# Tablet_LPF.net
KiCad netlist of a schematic drawn in EAGLE
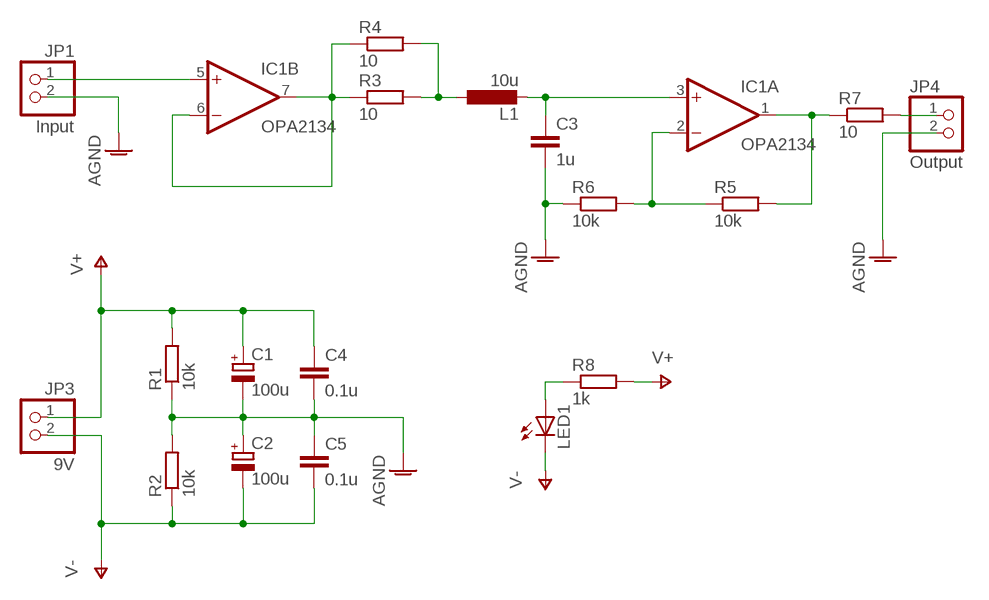
[diagram p0: schematic, sheet 1]

(export (version "E")
  (design (tool "Eeschema 10.0.6"))
  (components
    (comp (ref "C1")
      (value "100u")
      (footprint "eagle-import:E2,5-7")
      (libsource (lib "eagle-import") (part "CPOL-EUE2.5-7"))
    )
    (comp (ref "C2")
      (value "100u")
      (footprint "eagle-import:E2,5-7")
      (libsource (lib "eagle-import") (part "CPOL-EUE2.5-7"))
    )
    (comp (ref "C3")
      (value "1u")
      (footprint "eagle-import:C050-045X075")
      (libsource (lib "eagle-import") (part "C-EU050-045X075"))
    )
    (comp (ref "C4")
      (value "0.1u")
      (footprint "eagle-import:C025-024X044")
      (libsource (lib "eagle-import") (part "C-EU025-024X044"))
    )
    (comp (ref "C5")
      (value "0.1u")
      (footprint "eagle-import:C025-024X044")
      (libsource (lib "eagle-import") (part "C-EU025-024X044"))
    )
    (comp (ref "IC1")
      (value "OPA2134")
      (footprint "eagle-import:DIL08")
      (libsource (lib "eagle-import") (part "LM358N"))
    )
    (comp (ref "JP1")
      (value "Input")
      (footprint "eagle-import:1X02")
      (libsource (lib "eagle-import") (part "PINHD-1X2"))
    )
    (comp (ref "JP3")
      (value "9V")
      (footprint "eagle-import:1X02")
      (libsource (lib "eagle-import") (part "PINHD-1X2"))
    )
    (comp (ref "JP4")
      (value "Output")
      (footprint "eagle-import:1X02")
      (libsource (lib "eagle-import") (part "PINHD-1X2"))
    )
    (comp (ref "L1")
      (value "10u")
      (footprint "eagle-import:6000-XXXX-RC")
      (libsource (lib "eagle-import") (part "L-EU6000-XXX-RC"))
    )
    (comp (ref "LED1")
      (value "LED3MM")
      (footprint "eagle-import:LED3MM")
      (libsource (lib "eagle-import") (part "LED3MM"))
    )
    (comp (ref "R1")
      (value "10k")
      (footprint "eagle-import:0207_7")
      (libsource (lib "eagle-import") (part "R-EU_0207/7"))
    )
    (comp (ref "R2")
      (value "10k")
      (footprint "eagle-import:0207_7")
      (libsource (lib "eagle-import") (part "R-EU_0207/7"))
    )
    (comp (ref "R3")
      (value "10")
      (footprint "eagle-import:0207_7")
      (libsource (lib "eagle-import") (part "R-EU_0207/7"))
    )
    (comp (ref "R4")
      (value "10")
      (footprint "eagle-import:0207_7")
      (libsource (lib "eagle-import") (part "R-EU_0207/7"))
    )
    (comp (ref "R5")
      (value "10k")
      (footprint "eagle-import:0207_7")
      (libsource (lib "eagle-import") (part "R-EU_0207/7"))
    )
    (comp (ref "R6")
      (value "10k")
      (footprint "eagle-import:0207_7")
      (libsource (lib "eagle-import") (part "R-EU_0207/7"))
    )
    (comp (ref "R7")
      (value "10")
      (footprint "eagle-import:0207_7")
      (libsource (lib "eagle-import") (part "R-EU_0207/7"))
    )
    (comp (ref "R8")
      (value "1k")
      (footprint "eagle-import:0207_7")
      (libsource (lib "eagle-import") (part "R-EU_0207/7"))
    )
  )
  (nets
    (net (code "1") (name "AGND") (class "Default")
      (node (ref "C1") (pin "-") (pinfunction "-_-") (pintype "passive"))
      (node (ref "C2") (pin "+") (pinfunction "+_+") (pintype "passive"))
      (node (ref "C3") (pin "2") (pinfunction "2_2") (pintype "passive"))
      (node (ref "C4") (pin "2") (pinfunction "2_2") (pintype "passive"))
      (node (ref "C5") (pin "1") (pinfunction "1_1") (pintype "passive"))
      (node (ref "JP1") (pin "2") (pinfunction "2_2") (pintype "passive"))
      (node (ref "JP4") (pin "2") (pinfunction "2_2") (pintype "passive"))
      (node (ref "R1") (pin "1") (pinfunction "1_1") (pintype "passive"))
      (node (ref "R2") (pin "2") (pinfunction "2_2") (pintype "passive"))
      (node (ref "R6") (pin "1") (pinfunction "1_1") (pintype "passive"))
    )
    (net (code "2") (name "Net-(IC1A-+IN)") (class "Default")
      (node (ref "C3") (pin "1") (pinfunction "1_1") (pintype "passive"))
      (node (ref "IC1") (pin "3") (pinfunction "+IN_3") (pintype "input"))
      (node (ref "L1") (pin "2") (pinfunction "2_2") (pintype "passive"))
    )
    (net (code "3") (name "Net-(IC1A--IN)") (class "Default")
      (node (ref "IC1") (pin "2") (pinfunction "-IN_2") (pintype "input"))
      (node (ref "R5") (pin "1") (pinfunction "1_1") (pintype "passive"))
      (node (ref "R6") (pin "2") (pinfunction "2_2") (pintype "passive"))
    )
    (net (code "4") (name "Net-(IC1A-OUT)") (class "Default")
      (node (ref "IC1") (pin "1") (pinfunction "OUT_1") (pintype "output"))
      (node (ref "R5") (pin "2") (pinfunction "2_2") (pintype "passive"))
      (node (ref "R7") (pin "1") (pinfunction "1_1") (pintype "passive"))
    )
    (net (code "5") (name "Net-(IC1B-+IN)") (class "Default")
      (node (ref "IC1") (pin "5") (pinfunction "+IN_5") (pintype "input"))
      (node (ref "JP1") (pin "1") (pinfunction "1_1") (pintype "passive"))
    )
    (net (code "6") (name "Net-(IC1B--IN)") (class "Default")
      (node (ref "IC1") (pin "6") (pinfunction "-IN_6") (pintype "input"))
      (node (ref "IC1") (pin "7") (pinfunction "OUT_7") (pintype "output"))
      (node (ref "R3") (pin "1") (pinfunction "1_1") (pintype "passive"))
      (node (ref "R4") (pin "1") (pinfunction "1_1") (pintype "passive"))
    )
    (net (code "7") (name "Net-(JP4-Pad1)") (class "Default")
      (node (ref "JP4") (pin "1") (pinfunction "1_1") (pintype "passive"))
      (node (ref "R7") (pin "2") (pinfunction "2_2") (pintype "passive"))
    )
    (net (code "8") (name "Net-(L1-Pad1)") (class "Default")
      (node (ref "L1") (pin "1") (pinfunction "1_1") (pintype "passive"))
      (node (ref "R3") (pin "2") (pinfunction "2_2") (pintype "passive"))
      (node (ref "R4") (pin "2") (pinfunction "2_2") (pintype "passive"))
    )
    (net (code "9") (name "Net-(LED1-PadA)") (class "Default")
      (node (ref "LED1") (pin "A") (pinfunction "A_A") (pintype "passive"))
      (node (ref "R8") (pin "1") (pinfunction "1_1") (pintype "passive"))
    )
    (net (code "10") (name "V+") (class "Default")
      (node (ref "C1") (pin "+") (pinfunction "+_+") (pintype "passive"))
      (node (ref "C4") (pin "1") (pinfunction "1_1") (pintype "passive"))
      (node (ref "JP3") (pin "1") (pinfunction "1_1") (pintype "passive"))
      (node (ref "R1") (pin "2") (pinfunction "2_2") (pintype "passive"))
      (node (ref "R8") (pin "2") (pinfunction "2_2") (pintype "passive"))
    )
    (net (code "11") (name "V-") (class "Default")
      (node (ref "C2") (pin "-") (pinfunction "-_-") (pintype "passive"))
      (node (ref "C5") (pin "2") (pinfunction "2_2") (pintype "passive"))
      (node (ref "JP3") (pin "2") (pinfunction "2_2") (pintype "passive"))
      (node (ref "LED1") (pin "K") (pinfunction "C_K") (pintype "passive"))
      (node (ref "R2") (pin "1") (pinfunction "1_1") (pintype "passive"))
    )
  )
)
